# SCH_PianoBoard_2024-09-13.net
KiCad netlist of a schematic drawn in EasyEDA
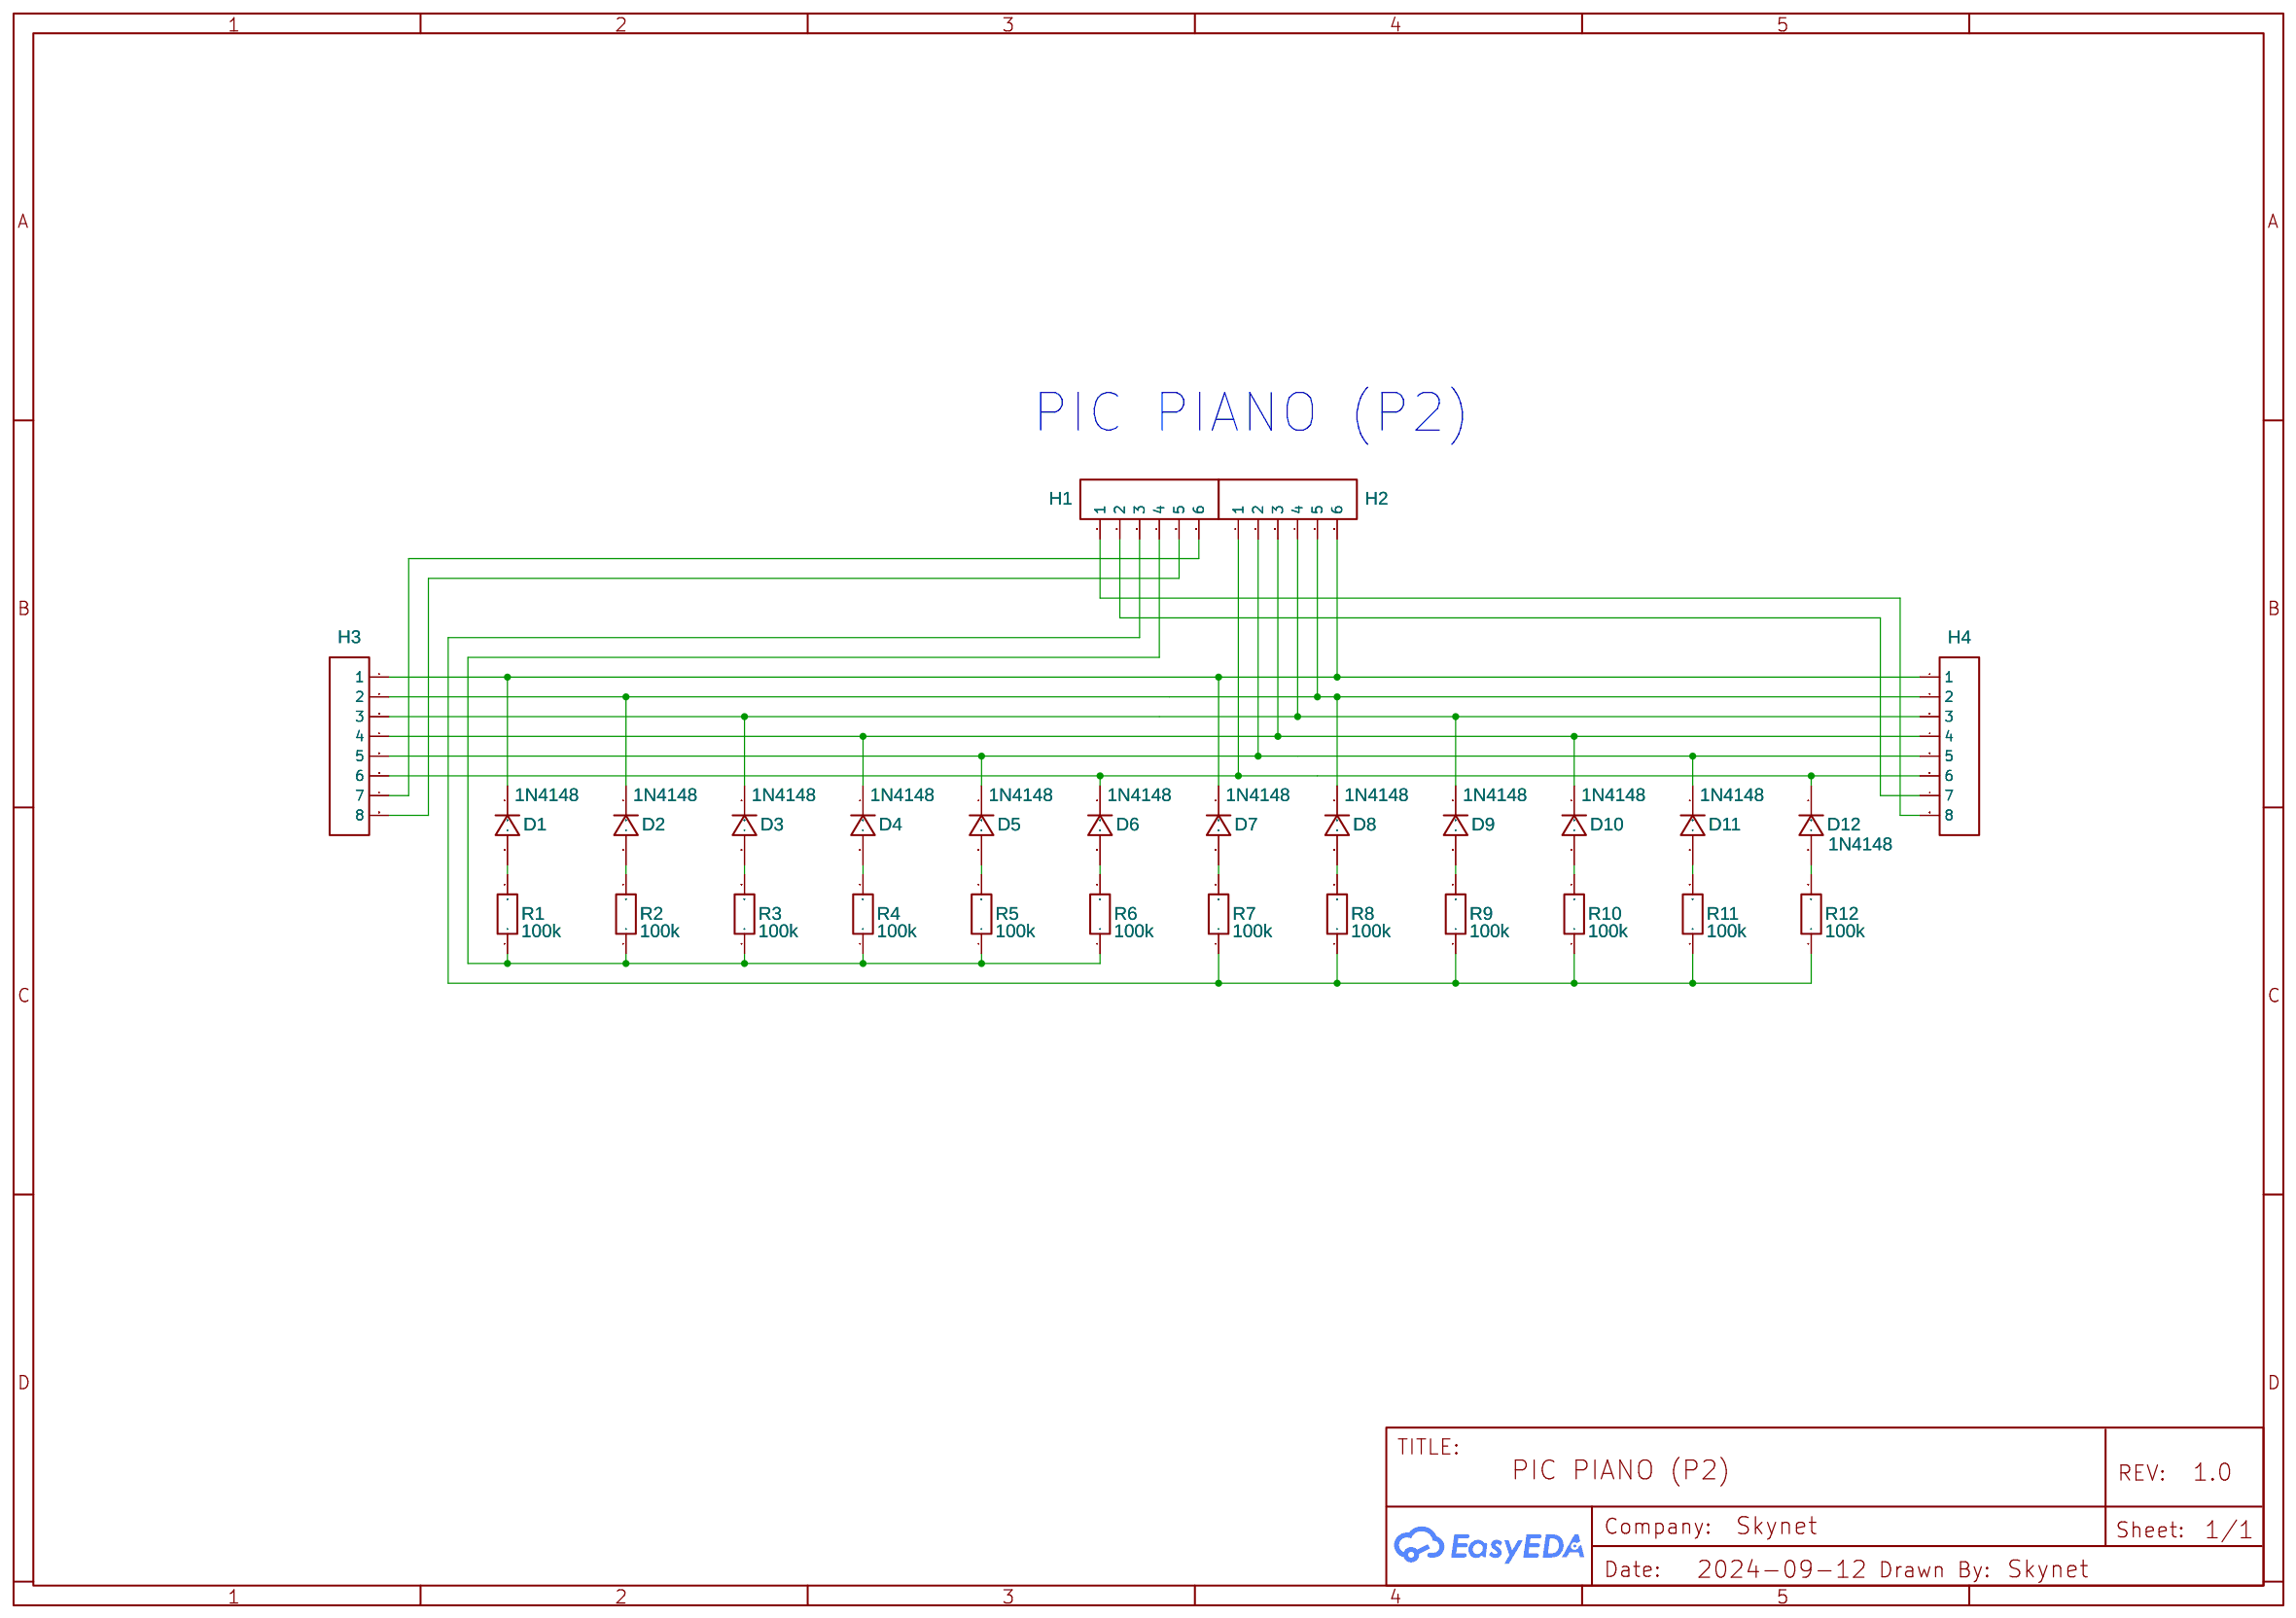
[diagram p0: schematic sheet]

(export (version "E")
  (design (tool "Eeschema 10.0.6"))
  (components
    (comp (ref "D1")
      (value "1N4148")
      (fields (field (name "Manufacturer Part") "1N4148WX-TP") (field (name "Manufacturer") "MCC(美微科)"))
      (libsource (lib "") (part "1N4148WX-TP"))
    )
    (comp (ref "D2")
      (value "1N4148")
      (fields (field (name "Manufacturer Part") "1N4148WX-TP") (field (name "Manufacturer") "MCC(美微科)"))
      (libsource (lib "") (part "1N4148WX-TP"))
    )
    (comp (ref "D3")
      (value "1N4148")
      (fields (field (name "Manufacturer Part") "1N4148WX-TP") (field (name "Manufacturer") "MCC(美微科)"))
      (libsource (lib "") (part "1N4148WX-TP"))
    )
    (comp (ref "D4")
      (value "1N4148")
      (fields (field (name "Manufacturer Part") "1N4148WX-TP") (field (name "Manufacturer") "MCC(美微科)"))
      (libsource (lib "") (part "1N4148WX-TP"))
    )
    (comp (ref "D5")
      (value "1N4148")
      (fields (field (name "Manufacturer Part") "1N4148WX-TP") (field (name "Manufacturer") "MCC(美微科)"))
      (libsource (lib "") (part "1N4148WX-TP"))
    )
    (comp (ref "D6")
      (value "1N4148")
      (fields (field (name "Manufacturer Part") "1N4148WX-TP") (field (name "Manufacturer") "MCC(美微科)"))
      (libsource (lib "") (part "1N4148WX-TP"))
    )
    (comp (ref "D7")
      (value "1N4148")
      (fields (field (name "Manufacturer Part") "1N4148WX-TP") (field (name "Manufacturer") "MCC(美微科)"))
      (libsource (lib "") (part "1N4148WX-TP"))
    )
    (comp (ref "D8")
      (value "1N4148")
      (fields (field (name "Manufacturer Part") "1N4148WX-TP") (field (name "Manufacturer") "MCC(美微科)"))
      (libsource (lib "") (part "1N4148WX-TP"))
    )
    (comp (ref "D9")
      (value "1N4148")
      (fields (field (name "Manufacturer Part") "1N4148WX-TP") (field (name "Manufacturer") "MCC(美微科)"))
      (libsource (lib "") (part "1N4148WX-TP"))
    )
    (comp (ref "D10")
      (value "1N4148")
      (fields (field (name "Manufacturer Part") "1N4148WX-TP") (field (name "Manufacturer") "MCC(美微科)"))
      (libsource (lib "") (part "1N4148WX-TP"))
    )
    (comp (ref "D11")
      (value "1N4148")
      (fields (field (name "Manufacturer Part") "1N4148WX-TP") (field (name "Manufacturer") "MCC(美微科)"))
      (libsource (lib "") (part "1N4148WX-TP"))
    )
    (comp (ref "D12")
      (value "1N4148")
      (fields (field (name "Manufacturer Part") "1N4148WX-TP") (field (name "Manufacturer") "MCC(美微科)"))
      (libsource (lib "") (part "1N4148WX-TP"))
    )
    (comp (ref "H1") (value "HDR-F-2.54_1x6") (libsource (lib "") (part "HDR-F-2.54_1x6")))
    (comp (ref "H2") (value "HDR-F-2.54_1x6") (libsource (lib "") (part "HDR-F-2.54_1x6")))
    (comp (ref "H3") (value "HDR-F-2.54_1x8") (libsource (lib "") (part "HDR-F-2.54_1x8")))
    (comp (ref "H4") (value "HDR-F-2.54_1x8") (libsource (lib "") (part "HDR-F-2.54_1x8_1")))
    (comp (ref "R1") (value "100k") (libsource (lib "") (part "R_0603_EU")))
    (comp (ref "R2") (value "100k") (libsource (lib "") (part "R_0603_EU")))
    (comp (ref "R3") (value "100k") (libsource (lib "") (part "R_0603_EU")))
    (comp (ref "R4") (value "100k") (libsource (lib "") (part "R_0603_EU")))
    (comp (ref "R5") (value "100k") (libsource (lib "") (part "R_0603_EU")))
    (comp (ref "R6") (value "100k") (libsource (lib "") (part "R_0603_EU")))
    (comp (ref "R7") (value "100k") (libsource (lib "") (part "R_0603_EU")))
    (comp (ref "R8") (value "100k") (libsource (lib "") (part "R_0603_EU")))
    (comp (ref "R9") (value "100k") (libsource (lib "") (part "R_0603_EU")))
    (comp (ref "R10") (value "100k") (libsource (lib "") (part "R_0603_EU")))
    (comp (ref "R11") (value "100k") (libsource (lib "") (part "R_0603_EU")))
    (comp (ref "R12") (value "100k") (libsource (lib "") (part "R_0603_EU")))
  )
  (nets
    (net (code "1") (name "Net-(D1-A)") (class "Default")
      (node (ref "D1") (pin "2") (pinfunction "A_2") (pintype "unspecified"))
      (node (ref "R1") (pin "2") (pinfunction "2_2") (pintype "unspecified"))
    )
    (net (code "2") (name "Net-(D1-C)") (class "Default")
      (node (ref "D1") (pin "1") (pinfunction "C_1") (pintype "unspecified"))
      (node (ref "D7") (pin "1") (pinfunction "C_1") (pintype "unspecified"))
      (node (ref "H2") (pin "6") (pinfunction "6_6") (pintype "input"))
      (node (ref "H3") (pin "1") (pinfunction "1_1") (pintype "unspecified"))
      (node (ref "H4") (pin "1") (pinfunction "1_1") (pintype "unspecified"))
    )
    (net (code "3") (name "Net-(D2-A)") (class "Default")
      (node (ref "D2") (pin "2") (pinfunction "A_2") (pintype "unspecified"))
      (node (ref "R2") (pin "2") (pinfunction "2_2") (pintype "unspecified"))
    )
    (net (code "4") (name "Net-(D2-C)") (class "Default")
      (node (ref "D2") (pin "1") (pinfunction "C_1") (pintype "unspecified"))
      (node (ref "D8") (pin "1") (pinfunction "C_1") (pintype "unspecified"))
      (node (ref "H2") (pin "5") (pinfunction "5_5") (pintype "input"))
      (node (ref "H3") (pin "2") (pinfunction "2_2") (pintype "unspecified"))
      (node (ref "H4") (pin "2") (pinfunction "2_2") (pintype "unspecified"))
    )
    (net (code "5") (name "Net-(D3-A)") (class "Default")
      (node (ref "D3") (pin "2") (pinfunction "A_2") (pintype "unspecified"))
      (node (ref "R3") (pin "2") (pinfunction "2_2") (pintype "unspecified"))
    )
    (net (code "6") (name "Net-(D3-C)") (class "Default")
      (node (ref "D3") (pin "1") (pinfunction "C_1") (pintype "unspecified"))
      (node (ref "D9") (pin "1") (pinfunction "C_1") (pintype "unspecified"))
      (node (ref "H2") (pin "4") (pinfunction "4_4") (pintype "input"))
      (node (ref "H3") (pin "3") (pinfunction "3_3") (pintype "unspecified"))
      (node (ref "H4") (pin "3") (pinfunction "3_3") (pintype "unspecified"))
    )
    (net (code "7") (name "Net-(D4-A)") (class "Default")
      (node (ref "D4") (pin "2") (pinfunction "A_2") (pintype "unspecified"))
      (node (ref "R4") (pin "2") (pinfunction "2_2") (pintype "unspecified"))
    )
    (net (code "8") (name "Net-(D5-A)") (class "Default")
      (node (ref "D5") (pin "2") (pinfunction "A_2") (pintype "unspecified"))
      (node (ref "R5") (pin "2") (pinfunction "2_2") (pintype "unspecified"))
    )
    (net (code "9") (name "Net-(D6-A)") (class "Default")
      (node (ref "D6") (pin "2") (pinfunction "A_2") (pintype "unspecified"))
      (node (ref "R6") (pin "2") (pinfunction "2_2") (pintype "unspecified"))
    )
    (net (code "10") (name "Net-(D7-A)") (class "Default")
      (node (ref "D7") (pin "2") (pinfunction "A_2") (pintype "unspecified"))
      (node (ref "R7") (pin "2") (pinfunction "2_2") (pintype "unspecified"))
    )
    (net (code "11") (name "Net-(D8-A)") (class "Default")
      (node (ref "D8") (pin "2") (pinfunction "A_2") (pintype "unspecified"))
      (node (ref "R8") (pin "2") (pinfunction "2_2") (pintype "unspecified"))
    )
    (net (code "12") (name "Net-(D9-A)") (class "Default")
      (node (ref "D9") (pin "2") (pinfunction "A_2") (pintype "unspecified"))
      (node (ref "R9") (pin "2") (pinfunction "2_2") (pintype "unspecified"))
    )
    (net (code "13") (name "Net-(D10-A)") (class "Default")
      (node (ref "D10") (pin "2") (pinfunction "A_2") (pintype "unspecified"))
      (node (ref "R10") (pin "2") (pinfunction "2_2") (pintype "unspecified"))
    )
    (net (code "14") (name "Net-(D10-C)") (class "Default")
      (node (ref "D10") (pin "1") (pinfunction "C_1") (pintype "unspecified"))
      (node (ref "D4") (pin "1") (pinfunction "C_1") (pintype "unspecified"))
      (node (ref "H2") (pin "3") (pinfunction "3_3") (pintype "input"))
      (node (ref "H3") (pin "4") (pinfunction "4_4") (pintype "unspecified"))
      (node (ref "H4") (pin "4") (pinfunction "4_4") (pintype "unspecified"))
    )
    (net (code "15") (name "Net-(D11-A)") (class "Default")
      (node (ref "D11") (pin "2") (pinfunction "A_2") (pintype "unspecified"))
      (node (ref "R11") (pin "2") (pinfunction "2_2") (pintype "unspecified"))
    )
    (net (code "16") (name "Net-(D11-C)") (class "Default")
      (node (ref "D11") (pin "1") (pinfunction "C_1") (pintype "unspecified"))
      (node (ref "D5") (pin "1") (pinfunction "C_1") (pintype "unspecified"))
      (node (ref "H2") (pin "2") (pinfunction "2_2") (pintype "input"))
      (node (ref "H3") (pin "5") (pinfunction "5_5") (pintype "unspecified"))
      (node (ref "H4") (pin "5") (pinfunction "5_5") (pintype "unspecified"))
    )
    (net (code "17") (name "Net-(D12-A)") (class "Default")
      (node (ref "D12") (pin "2") (pinfunction "A_2") (pintype "unspecified"))
      (node (ref "R12") (pin "2") (pinfunction "2_2") (pintype "unspecified"))
    )
    (net (code "18") (name "Net-(D12-C)") (class "Default")
      (node (ref "D12") (pin "1") (pinfunction "C_1") (pintype "unspecified"))
      (node (ref "D6") (pin "1") (pinfunction "C_1") (pintype "unspecified"))
      (node (ref "H2") (pin "1") (pinfunction "1_1") (pintype "input"))
      (node (ref "H3") (pin "6") (pinfunction "6_6") (pintype "unspecified"))
      (node (ref "H4") (pin "6") (pinfunction "6_6") (pintype "unspecified"))
    )
    (net (code "19") (name "Net-(H1-Pad1)") (class "Default")
      (node (ref "H1") (pin "1") (pinfunction "1_1") (pintype "input"))
      (node (ref "H4") (pin "8") (pinfunction "8_8") (pintype "unspecified"))
    )
    (net (code "20") (name "Net-(H1-Pad2)") (class "Default")
      (node (ref "H1") (pin "2") (pinfunction "2_2") (pintype "input"))
      (node (ref "H4") (pin "7") (pinfunction "7_7") (pintype "unspecified"))
    )
    (net (code "21") (name "Net-(H1-Pad3)") (class "Default")
      (node (ref "H1") (pin "3") (pinfunction "3_3") (pintype "input"))
      (node (ref "R10") (pin "1") (pinfunction "1_1") (pintype "unspecified"))
      (node (ref "R11") (pin "1") (pinfunction "1_1") (pintype "unspecified"))
      (node (ref "R12") (pin "1") (pinfunction "1_1") (pintype "unspecified"))
      (node (ref "R7") (pin "1") (pinfunction "1_1") (pintype "unspecified"))
      (node (ref "R8") (pin "1") (pinfunction "1_1") (pintype "unspecified"))
      (node (ref "R9") (pin "1") (pinfunction "1_1") (pintype "unspecified"))
    )
    (net (code "22") (name "Net-(H1-Pad4)") (class "Default")
      (node (ref "H1") (pin "4") (pinfunction "4_4") (pintype "input"))
      (node (ref "R1") (pin "1") (pinfunction "1_1") (pintype "unspecified"))
      (node (ref "R2") (pin "1") (pinfunction "1_1") (pintype "unspecified"))
      (node (ref "R3") (pin "1") (pinfunction "1_1") (pintype "unspecified"))
      (node (ref "R4") (pin "1") (pinfunction "1_1") (pintype "unspecified"))
      (node (ref "R5") (pin "1") (pinfunction "1_1") (pintype "unspecified"))
      (node (ref "R6") (pin "1") (pinfunction "1_1") (pintype "unspecified"))
    )
    (net (code "23") (name "Net-(H1-Pad5)") (class "Default")
      (node (ref "H1") (pin "5") (pinfunction "5_5") (pintype "input"))
      (node (ref "H3") (pin "8") (pinfunction "8_8") (pintype "unspecified"))
    )
    (net (code "24") (name "Net-(H1-Pad6)") (class "Default")
      (node (ref "H1") (pin "6") (pinfunction "6_6") (pintype "input"))
      (node (ref "H3") (pin "7") (pinfunction "7_7") (pintype "unspecified"))
    )
  )
)
